# ProPrj_LED__2025-11-30-18-16-02.net
KiCad netlist of a schematic drawn in EasyEDA Pro
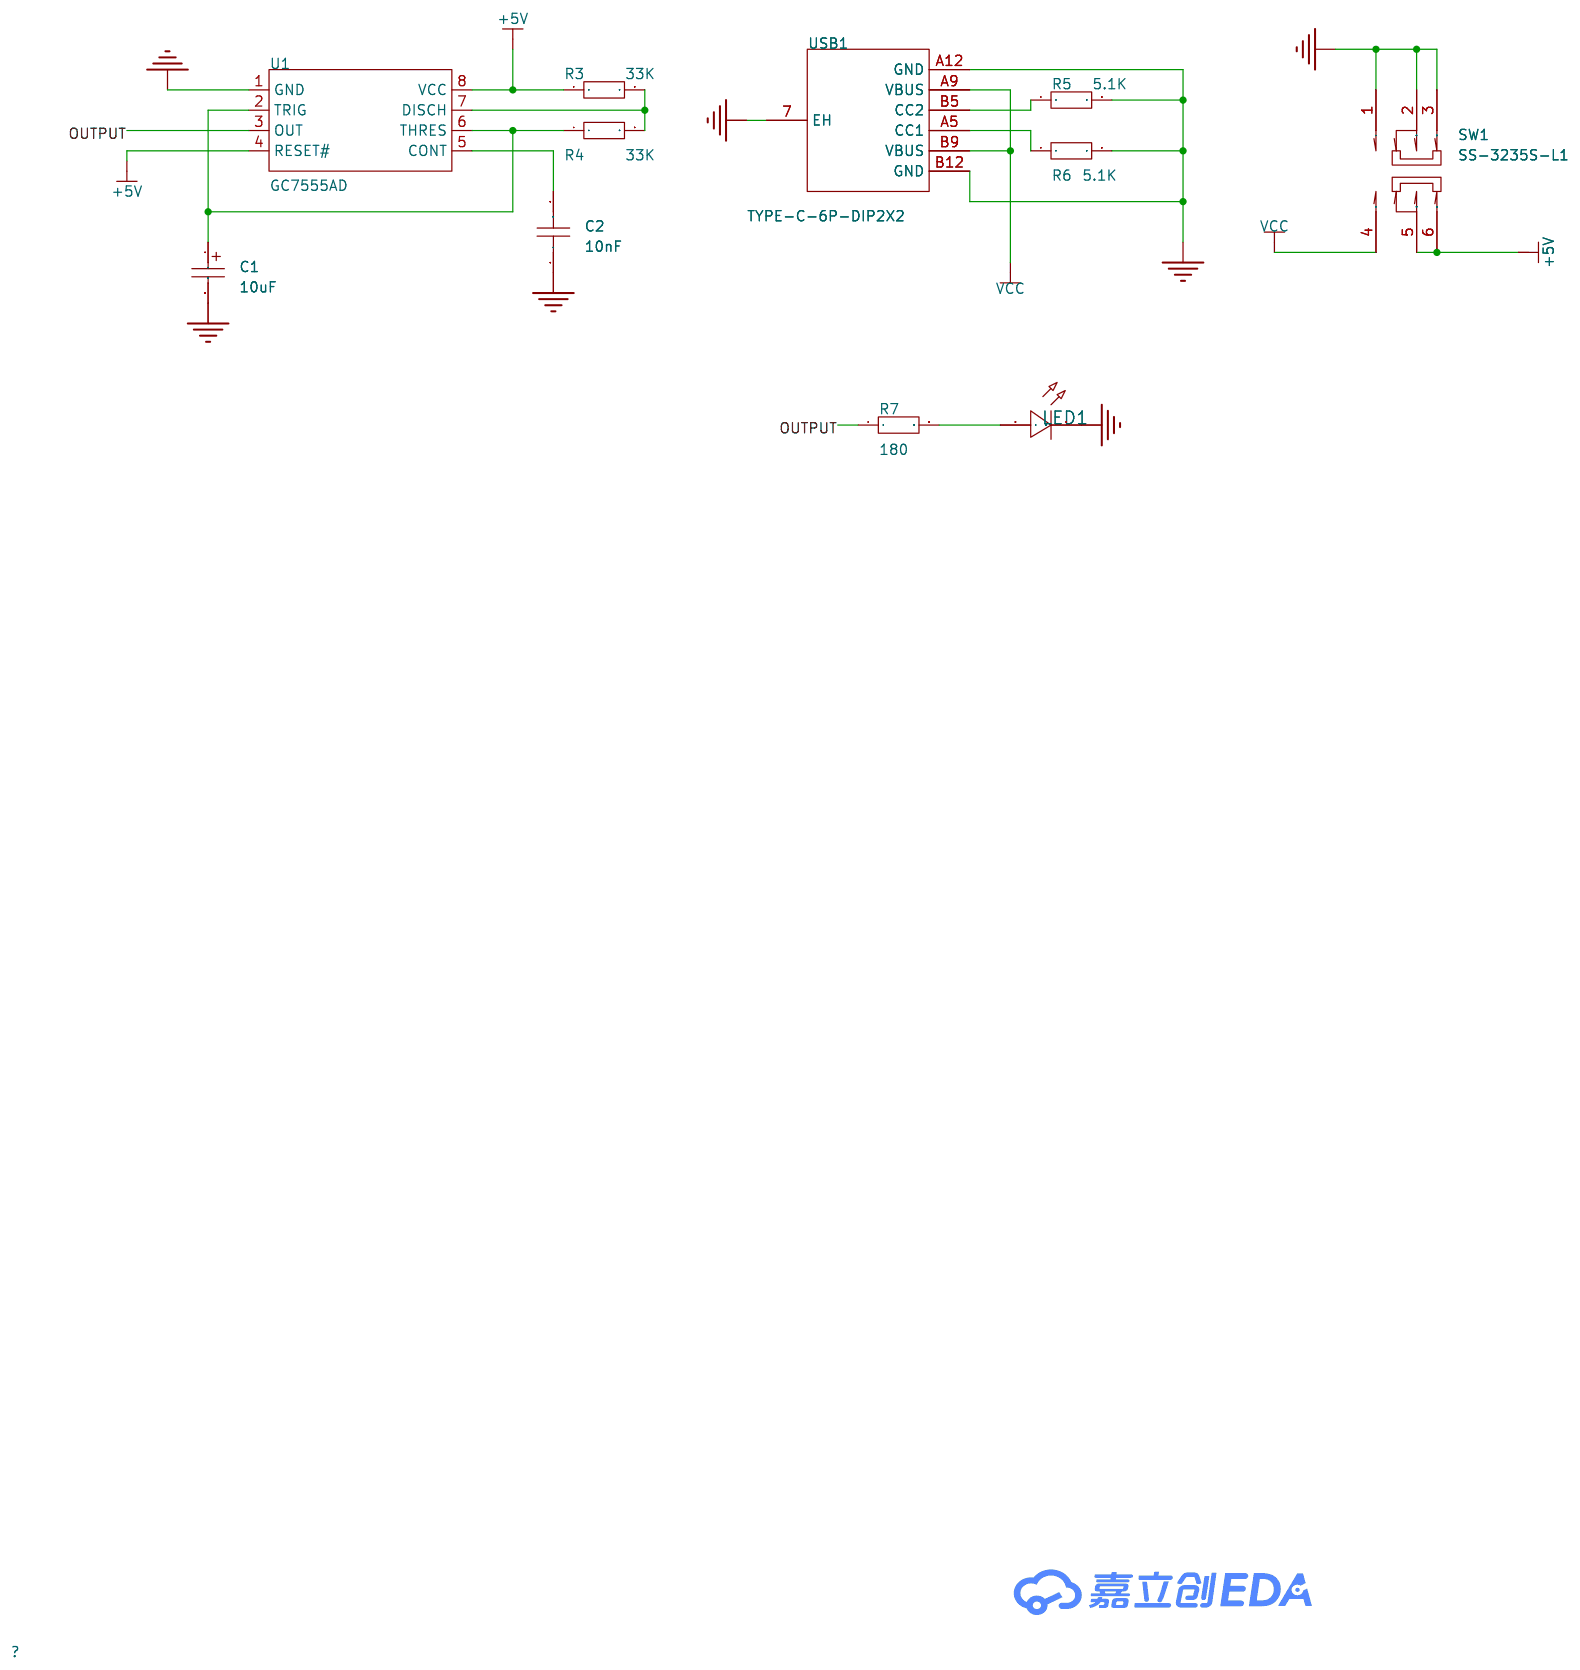
[diagram p0: schematic sheet]

(export (version "E")
  (design (tool "Eeschema 10.0.6"))
  (components
    (comp (ref "C1")
      (value "10uF")
      (footprint "easyedapro:C_Ele_SMD_3x5.4mm")
      (libsource (lib "easyedapro") (part "CAP"))
    )
    (comp (ref "C2")
      (value "10nF")
      (footprint "easyedapro:C0603")
      (libsource (lib "easyedapro") (part "Capacitance"))
    )
    (comp (ref "LED1")
      (value "~")
      (footprint "easyedapro:LED_0603")
      (libsource (lib "easyedapro") (part "LED_R"))
    )
    (comp (ref "R3") (value "33K") (footprint "easyedapro:R0805") (libsource (lib "easyedapro") (part "电阻")))
    (comp (ref "R4") (value "33K") (footprint "easyedapro:R0805") (libsource (lib "easyedapro") (part "电阻")))
    (comp (ref "R5") (value "5.1K") (footprint "easyedapro:R0805") (libsource (lib "easyedapro") (part "电阻")))
    (comp (ref "R6") (value "5.1K") (footprint "easyedapro:R0805") (libsource (lib "easyedapro") (part "电阻")))
    (comp (ref "R7") (value "180") (footprint "easyedapro:R0805") (libsource (lib "easyedapro") (part "电阻")))
    (comp (ref "SW1")
      (value "SS-3235S-L1")
      (footprint "easyedapro:SW-SMD_SS-3235S-LX")
      (description "电路结构:双刀双掷;安装方式:卧贴;开关颜色:黑色;额定电流:50mA;额定电压:12V;工作寿命:1万次;")
      (fields (field (name "Manufacturer") "XKB Connection(中国星坤)"))
      (libsource (lib "easyedapro") (part "SS-3235S-L1"))
    )
    (comp (ref "U1")
      (value "GC7555AD")
      (footprint "easyedapro:PDIP-8_L9.5-W6.4-P2.54-LS7.6-BL")
      (description "通用计时器：时基电路；计时；脉冲产生；满足用户（至少工业级）自主可控的需求。")
      (fields (field (name "Manufacturer") "Sungine(双竞集成)"))
      (libsource (lib "easyedapro") (part "GC7555AD"))
    )
    (comp (ref "USB1")
      (value "TYPE-C-6P-DIP2X2")
      (footprint "easyedapro:TYPE-C-SMD_TYPE-C-6P")
      (libsource (lib "easyedapro") (part "TYPE-C-6P-DIP2X2"))
    )
  )
  (nets
    (net (code "1") (name "+5V") (class "Default")
      (node (ref "R3") (pin "1") (pinfunction "1_1") (pintype "input"))
      (node (ref "SW1") (pin "5") (pinfunction "5_5") (pintype "unspecified"))
      (node (ref "SW1") (pin "6") (pinfunction "6_6") (pintype "unspecified"))
      (node (ref "U1") (pin "4") (pinfunction "RESET#_4") (pintype "unspecified"))
      (node (ref "U1") (pin "8") (pinfunction "VCC_8") (pintype "unspecified"))
    )
    (net (code "2") (name "/OUTPUT") (class "Default")
      (node (ref "R7") (pin "1") (pinfunction "1_1") (pintype "input"))
      (node (ref "U1") (pin "3") (pinfunction "OUT_3") (pintype "unspecified"))
    )
    (net (code "3") (name "GND") (class "Default")
      (node (ref "C1") (pin "2") (pinfunction "2_2") (pintype "input"))
      (node (ref "C2") (pin "1") (pinfunction "1_1") (pintype "input"))
      (node (ref "LED1") (pin "1") (pinfunction "C_1") (pintype "input"))
      (node (ref "R5") (pin "2") (pinfunction "2_2") (pintype "input"))
      (node (ref "R6") (pin "2") (pinfunction "2_2") (pintype "input"))
      (node (ref "SW1") (pin "1") (pinfunction "1_1") (pintype "unspecified"))
      (node (ref "SW1") (pin "2") (pinfunction "2_2") (pintype "unspecified"))
      (node (ref "SW1") (pin "3") (pinfunction "3_3") (pintype "unspecified"))
      (node (ref "U1") (pin "1") (pinfunction "GND_1") (pintype "unspecified"))
      (node (ref "USB1") (pin "7") (pinfunction "EH_7") (pintype "unspecified"))
      (node (ref "USB1") (pin "A12") (pinfunction "GND_A12") (pintype "unspecified"))
      (node (ref "USB1") (pin "B12") (pinfunction "GND_B12") (pintype "unspecified"))
    )
    (net (code "4") (name "Net-(LED1-A)") (class "Default")
      (node (ref "LED1") (pin "2") (pinfunction "A_2") (pintype "input"))
      (node (ref "R7") (pin "2") (pinfunction "2_2") (pintype "input"))
    )
    (net (code "5") (name "Net-(U1-CONT)") (class "Default")
      (node (ref "C2") (pin "2") (pinfunction "2_2") (pintype "input"))
      (node (ref "U1") (pin "5") (pinfunction "CONT_5") (pintype "unspecified"))
    )
    (net (code "6") (name "Net-(U1-DISCH)") (class "Default")
      (node (ref "R3") (pin "2") (pinfunction "2_2") (pintype "input"))
      (node (ref "R4") (pin "2") (pinfunction "2_2") (pintype "input"))
      (node (ref "U1") (pin "7") (pinfunction "DISCH_7") (pintype "unspecified"))
    )
    (net (code "7") (name "Net-(U1-THRES)") (class "Default")
      (node (ref "C1") (pin "1") (pinfunction "1_1") (pintype "input"))
      (node (ref "R4") (pin "1") (pinfunction "1_1") (pintype "input"))
      (node (ref "U1") (pin "2") (pinfunction "TRIG_2") (pintype "unspecified"))
      (node (ref "U1") (pin "6") (pinfunction "THRES_6") (pintype "unspecified"))
    )
    (net (code "8") (name "Net-(USB1-CC1)") (class "Default")
      (node (ref "R6") (pin "1") (pinfunction "1_1") (pintype "input"))
      (node (ref "USB1") (pin "A5") (pinfunction "CC1_A5") (pintype "unspecified"))
    )
    (net (code "9") (name "Net-(USB1-CC2)") (class "Default")
      (node (ref "R5") (pin "1") (pinfunction "1_1") (pintype "input"))
      (node (ref "USB1") (pin "B5") (pinfunction "CC2_B5") (pintype "unspecified"))
    )
    (net (code "10") (name "VCC") (class "Default")
      (node (ref "SW1") (pin "4") (pinfunction "4_4") (pintype "unspecified"))
      (node (ref "USB1") (pin "A9") (pinfunction "VBUS_A9") (pintype "unspecified"))
      (node (ref "USB1") (pin "B9") (pinfunction "VBUS_B9") (pintype "unspecified"))
    )
  )
)
